# Simon.net
KiCad netlist of a schematic drawn in EAGLE
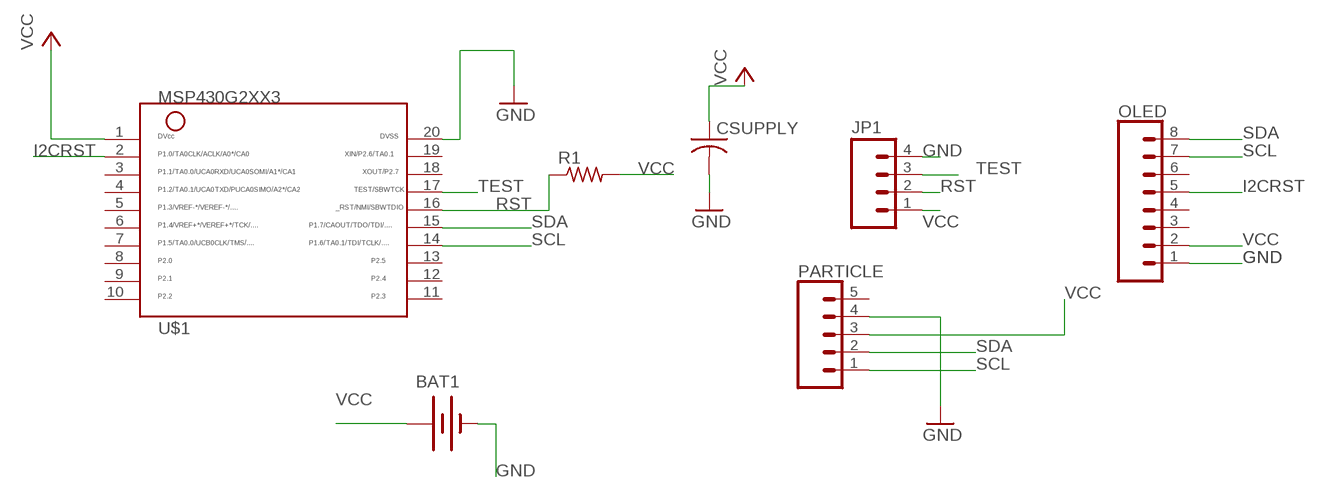
[diagram p0: schematic, sheet 1]

(export (version "E")
  (design (tool "Eeschema 10.0.6"))
  (components
    (comp (ref "BAT1")
      (value "BATTERYBU2032SM")
      (footprint "eagle-import:BU2032SM")
      (libsource (lib "eagle-import") (part "BATTERYBU2032SM"))
    )
    (comp (ref "CSUPPLY")
      (value "C-USC1206")
      (footprint "eagle-import:C1206")
      (libsource (lib "eagle-import") (part "C-USC1206"))
    )
    (comp (ref "JP1")
      (value "M04LOCK")
      (footprint "eagle-import:1X04_LOCK")
      (libsource (lib "eagle-import") (part "M04LOCK"))
    )
    (comp (ref "OLED")
      (value "CONN_08\"")
      (footprint "eagle-import:1X08")
      (libsource (lib "eagle-import") (part "CONN_08{dblquote}"))
    )
    (comp (ref "PARTICLE")
      (value "CONN_05")
      (footprint "eagle-import:1X05")
      (libsource (lib "eagle-import") (part "CONN_05"))
    )
    (comp (ref "R1")
      (value "R-US_R1206")
      (footprint "eagle-import:R1206")
      (libsource (lib "eagle-import") (part "R-US_R1206"))
    )
    (comp (ref "U$1")
      (value "MSP430G2XX3TSSOP")
      (footprint "eagle-import:PW20")
      (libsource (lib "eagle-import") (part "MSP430G2XX3TSSOP"))
    )
  )
  (nets
    (net (code "1") (name "/I2CRST") (class "Default")
      (node (ref "OLED") (pin "5") (pinfunction "5_5") (pintype "passive"))
      (node (ref "U$1") (pin "2") (pinfunction "2_2") (pintype "bidirectional"))
    )
    (net (code "2") (name "/RST") (class "Default")
      (node (ref "JP1") (pin "2") (pinfunction "2_2") (pintype "passive"))
      (node (ref "R1") (pin "1") (pinfunction "1_1") (pintype "passive"))
      (node (ref "U$1") (pin "16") (pinfunction "16_16") (pintype "bidirectional"))
    )
    (net (code "3") (name "/SCL") (class "Default")
      (node (ref "OLED") (pin "7") (pinfunction "7_7") (pintype "passive"))
      (node (ref "PARTICLE") (pin "1") (pinfunction "1_1") (pintype "passive"))
      (node (ref "U$1") (pin "14") (pinfunction "14_14") (pintype "bidirectional"))
    )
    (net (code "4") (name "/SDA") (class "Default")
      (node (ref "OLED") (pin "8") (pinfunction "8_8") (pintype "passive"))
      (node (ref "PARTICLE") (pin "2") (pinfunction "2_2") (pintype "passive"))
      (node (ref "U$1") (pin "15") (pinfunction "15_15") (pintype "bidirectional"))
    )
    (net (code "5") (name "/TEST") (class "Default")
      (node (ref "JP1") (pin "3") (pinfunction "3_3") (pintype "passive"))
      (node (ref "U$1") (pin "17") (pinfunction "17_17") (pintype "bidirectional"))
    )
    (net (code "6") (name "GND") (class "Default")
      (node (ref "BAT1") (pin "P$2") (pinfunction "-_P$2") (pintype "power_in"))
      (node (ref "CSUPPLY") (pin "2") (pinfunction "2_2") (pintype "passive"))
      (node (ref "JP1") (pin "4") (pinfunction "4_4") (pintype "passive"))
      (node (ref "OLED") (pin "1") (pinfunction "1_1") (pintype "passive"))
      (node (ref "PARTICLE") (pin "4") (pinfunction "4_4") (pintype "passive"))
      (node (ref "U$1") (pin "20") (pinfunction "20_20") (pintype "bidirectional"))
    )
    (net (code "7") (name "VCC") (class "Default")
      (node (ref "BAT1") (pin "P$1") (pinfunction "+_P$1") (pintype "power_in"))
      (node (ref "CSUPPLY") (pin "1") (pinfunction "1_1") (pintype "passive"))
      (node (ref "JP1") (pin "1") (pinfunction "1_1") (pintype "passive"))
      (node (ref "OLED") (pin "2") (pinfunction "2_2") (pintype "passive"))
      (node (ref "PARTICLE") (pin "3") (pinfunction "3_3") (pintype "passive"))
      (node (ref "R1") (pin "2") (pinfunction "2_2") (pintype "passive"))
      (node (ref "U$1") (pin "1") (pinfunction "1_1") (pintype "bidirectional"))
    )
    (net (code "8") (name "unconnected-(OLED-Pad3)") (class "Default")
      (node (ref "OLED") (pin "3") (pinfunction "3_3") (pintype "passive"))
    )
    (net (code "9") (name "unconnected-(OLED-Pad4)") (class "Default")
      (node (ref "OLED") (pin "4") (pinfunction "4_4") (pintype "passive"))
    )
    (net (code "10") (name "unconnected-(OLED-Pad6)") (class "Default")
      (node (ref "OLED") (pin "6") (pinfunction "6_6") (pintype "passive"))
    )
    (net (code "11") (name "unconnected-(PARTICLE-Pad5)") (class "Default")
      (node (ref "PARTICLE") (pin "5") (pinfunction "5_5") (pintype "passive"))
    )
    (net (code "12") (name "unconnected-(U$1-Pad3)") (class "Default")
      (node (ref "U$1") (pin "3") (pinfunction "3_3") (pintype "bidirectional"))
    )
    (net (code "13") (name "unconnected-(U$1-Pad4)") (class "Default")
      (node (ref "U$1") (pin "4") (pinfunction "4_4") (pintype "bidirectional"))
    )
    (net (code "14") (name "unconnected-(U$1-Pad5)") (class "Default")
      (node (ref "U$1") (pin "5") (pinfunction "5_5") (pintype "bidirectional"))
    )
    (net (code "15") (name "unconnected-(U$1-Pad6)") (class "Default")
      (node (ref "U$1") (pin "6") (pinfunction "6_6") (pintype "bidirectional"))
    )
    (net (code "16") (name "unconnected-(U$1-Pad7)") (class "Default")
      (node (ref "U$1") (pin "7") (pinfunction "7_7") (pintype "bidirectional"))
    )
    (net (code "17") (name "unconnected-(U$1-Pad8)") (class "Default")
      (node (ref "U$1") (pin "8") (pinfunction "8_8") (pintype "bidirectional"))
    )
    (net (code "18") (name "unconnected-(U$1-Pad9)") (class "Default")
      (node (ref "U$1") (pin "9") (pinfunction "9_9") (pintype "bidirectional"))
    )
    (net (code "19") (name "unconnected-(U$1-Pad10)") (class "Default")
      (node (ref "U$1") (pin "10") (pinfunction "10_10") (pintype "bidirectional"))
    )
    (net (code "20") (name "unconnected-(U$1-Pad11)") (class "Default")
      (node (ref "U$1") (pin "11") (pinfunction "11_11") (pintype "bidirectional"))
    )
    (net (code "21") (name "unconnected-(U$1-Pad12)") (class "Default")
      (node (ref "U$1") (pin "12") (pinfunction "12_12") (pintype "bidirectional"))
    )
    (net (code "22") (name "unconnected-(U$1-Pad13)") (class "Default")
      (node (ref "U$1") (pin "13") (pinfunction "13_13") (pintype "bidirectional"))
    )
    (net (code "23") (name "unconnected-(U$1-Pad18)") (class "Default")
      (node (ref "U$1") (pin "18") (pinfunction "18_18") (pintype "bidirectional"))
    )
    (net (code "24") (name "unconnected-(U$1-Pad19)") (class "Default")
      (node (ref "U$1") (pin "19") (pinfunction "19_19") (pintype "bidirectional"))
    )
  )
)
